# BT.net
KiCad netlist of a schematic drawn in Altium Designer
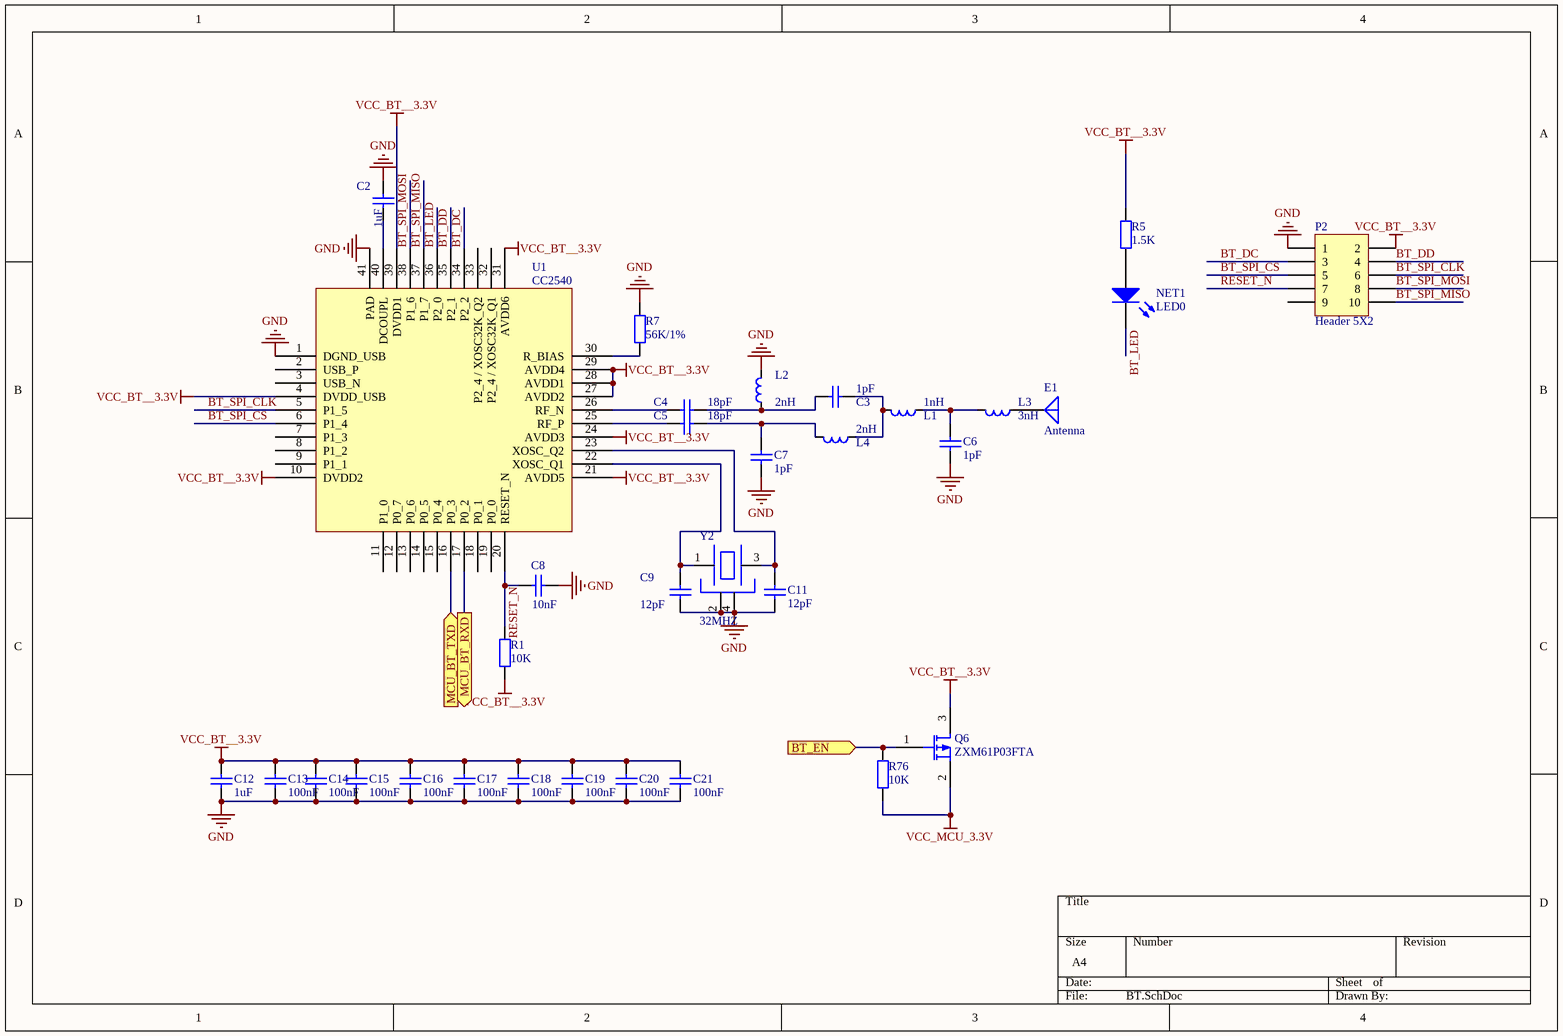
[diagram p0: BT.SchDoc]

(export (version "E")
  (design (tool "Eeschema 10.0.6"))
  (components
    (comp (ref "C2")
      (value "1uF")
      (footprint "0603C")
      (description "Capacitor")
      (fields (field (name "PUBLISHER") "Altium Limited"))
      (libsource (lib "Miscellaneous Devices") (part "Cap"))
    )
    (comp (ref "C3")
      (value "1pF")
      (footprint "0402C")
      (description "Capacitor")
      (fields (field (name "PUBLISHER") "Altium Limited"))
      (libsource (lib "Miscellaneous Devices") (part "Cap"))
    )
    (comp (ref "C4")
      (value "18pF")
      (footprint "0402C")
      (description "Capacitor")
      (fields (field (name "PUBLISHER") "Altium Limited"))
      (libsource (lib "Miscellaneous Devices") (part "Cap"))
    )
    (comp (ref "C5")
      (value "18pF")
      (footprint "0402C")
      (description "Capacitor")
      (fields (field (name "PUBLISHER") "Altium Limited"))
      (libsource (lib "Miscellaneous Devices") (part "Cap"))
    )
    (comp (ref "C6")
      (value "1pF")
      (footprint "0402C")
      (description "Capacitor")
      (fields (field (name "PUBLISHER") "Altium Limited"))
      (libsource (lib "Miscellaneous Devices") (part "Cap"))
    )
    (comp (ref "C7")
      (value "1pF")
      (footprint "0402C")
      (description "Capacitor")
      (fields (field (name "PUBLISHER") "Altium Limited"))
      (libsource (lib "Miscellaneous Devices") (part "Cap"))
    )
    (comp (ref "C8")
      (value "10nF")
      (footprint "0402C")
      (description "Capacitor")
      (fields (field (name "PUBLISHER") "Altium Limited"))
      (libsource (lib "Miscellaneous Devices") (part "Cap"))
    )
    (comp (ref "C9")
      (value "12pF")
      (footprint "0402C")
      (description "Capacitor")
      (fields (field (name "PUBLISHER") "Altium Limited"))
      (libsource (lib "Miscellaneous Devices") (part "Cap"))
    )
    (comp (ref "C11")
      (value "12pF")
      (footprint "0402C")
      (description "Capacitor")
      (fields (field (name "PUBLISHER") "Altium Limited"))
      (libsource (lib "Miscellaneous Devices") (part "Cap"))
    )
    (comp (ref "C12")
      (value "1uF")
      (footprint "0603C")
      (description "Capacitor")
      (fields (field (name "PUBLISHER") "Altium Limited"))
      (libsource (lib "Miscellaneous Devices") (part "Cap"))
    )
    (comp (ref "C13")
      (value "100nF")
      (footprint "0603C")
      (description "Capacitor")
      (fields (field (name "PUBLISHER") "Altium Limited"))
      (libsource (lib "Miscellaneous Devices") (part "Cap"))
    )
    (comp (ref "C14")
      (value "100nF")
      (footprint "0603C")
      (description "Capacitor")
      (fields (field (name "PUBLISHER") "Altium Limited"))
      (libsource (lib "Miscellaneous Devices") (part "Cap"))
    )
    (comp (ref "C15")
      (value "100nF")
      (footprint "0603C")
      (description "Capacitor")
      (fields (field (name "PUBLISHER") "Altium Limited"))
      (libsource (lib "Miscellaneous Devices") (part "Cap"))
    )
    (comp (ref "C16")
      (value "100nF")
      (footprint "0603C")
      (description "Capacitor")
      (fields (field (name "PUBLISHER") "Altium Limited"))
      (libsource (lib "Miscellaneous Devices") (part "Cap"))
    )
    (comp (ref "C17")
      (value "100nF")
      (footprint "0603C")
      (description "Capacitor")
      (fields (field (name "PUBLISHER") "Altium Limited"))
      (libsource (lib "Miscellaneous Devices") (part "Cap"))
    )
    (comp (ref "C18")
      (value "100nF")
      (footprint "0603C")
      (description "Capacitor")
      (fields (field (name "PUBLISHER") "Altium Limited"))
      (libsource (lib "Miscellaneous Devices") (part "Cap"))
    )
    (comp (ref "C19")
      (value "100nF")
      (footprint "0603C")
      (description "Capacitor")
      (fields (field (name "PUBLISHER") "Altium Limited"))
      (libsource (lib "Miscellaneous Devices") (part "Cap"))
    )
    (comp (ref "C20")
      (value "100nF")
      (footprint "0603C")
      (description "Capacitor")
      (fields (field (name "PUBLISHER") "Altium Limited"))
      (libsource (lib "Miscellaneous Devices") (part "Cap"))
    )
    (comp (ref "C21")
      (value "100nF")
      (footprint "0603C")
      (description "Capacitor")
      (fields (field (name "PUBLISHER") "Altium Limited"))
      (libsource (lib "Miscellaneous Devices") (part "Cap"))
    )
    (comp (ref "E1")
      (value "Antenna")
      (footprint "AN2051")
      (description "Generic Antenna")
      (fields (field (name "PUBLISHER") "Altium Limited"))
      (libsource (lib "Miscellaneous Devices") (part "Antenna"))
    )
    (comp (ref "L1") (value "1nH") (footprint "0402R") (description "L") (libsource (lib "*") (part "L_4")))
    (comp (ref "L2") (value "2nH") (footprint "0402R") (description "L") (libsource (lib "") (part "L_4_1")))
    (comp (ref "L3") (value "3nH") (footprint "0402R") (description "L") (libsource (lib "*") (part "L_4")))
    (comp (ref "L4") (value "2nH") (footprint "0402R") (description "L") (libsource (lib "*") (part "L_4")))
    (comp (ref "NET1")
      (value "LED0")
      (footprint "0603LED")
      (description "Typical INFRARED GaAs LED")
      (fields (field (name "PUBLISHER") "Altium Limited"))
      (libsource (lib "Miscellaneous Devices") (part "LED0"))
    )
    (comp (ref "P2")
      (value "Header 5X2")
      (footprint "HDR2X5")
      (description "Header, 5-Pin, Dual row")
      (fields (field (name "PUBLISHER") "Altium Limited"))
      (libsource (lib "Miscellaneous Connectors") (part "Header 5X2"))
    )
    (comp (ref "Q6")
      (value "ZXM61P03FTA")
      (footprint "SOT23-3")
      (description "ZXM61P03F")
      (fields (field (name "PUBLISHER") "Altium Limited"))
      (libsource (lib "Miscellaneous Devices") (part "MOSFET-P"))
    )
    (comp (ref "R1")
      (value "10K")
      (footprint "0603R")
      (description "Resistor")
      (fields (field (name "PUBLISHER") "Altium Limited"))
      (libsource (lib "Miscellaneous Devices") (part "Res2"))
    )
    (comp (ref "R5")
      (value "1.5K")
      (footprint "0603R")
      (description "Resistor")
      (fields (field (name "PUBLISHER") "Altium Limited"))
      (libsource (lib "Miscellaneous Devices") (part "Res2"))
    )
    (comp (ref "R7")
      (value "56K/1%")
      (footprint "0603R")
      (description "Resistor")
      (fields (field (name "PUBLISHER") "Altium Limited"))
      (libsource (lib "Miscellaneous Devices") (part "Res2"))
    )
    (comp (ref "R76")
      (value "10K")
      (footprint "0603R")
      (description "Resistor")
      (fields (field (name "PUBLISHER") "Altium Limited"))
      (libsource (lib "Miscellaneous Devices") (part "Res2"))
    )
    (comp (ref "U1")
      (value "CC2540")
      (footprint "QFN50P600X600X80-40N")
      (libsource (lib "stm32") (part "CC2540"))
    )
    (comp (ref "Y2")
      (value "32MHZ")
      (footprint "OSCILLATOR-3.2X2.5")
      (libsource (lib "Myself_1") (part "XTAL3"))
    )
  )
  (nets
    (net (code "1") (name "/BT_DC") (class "Default")
      (node (ref "P2") (pin "3") (pinfunction "3_3") (pintype "passive"))
      (node (ref "U1") (pin "34") (pinfunction "P2_2_34") (pintype "passive"))
    )
    (net (code "2") (name "/BT_DD") (class "Default")
      (node (ref "P2") (pin "4") (pinfunction "4_4") (pintype "passive"))
      (node (ref "U1") (pin "35") (pinfunction "P2_1_35") (pintype "passive"))
    )
    (net (code "3") (name "/BT_EN") (class "Default")
      (node (ref "Q6") (pin "1") (pinfunction "G_1") (pintype "passive"))
      (node (ref "R76") (pin "1") (pinfunction "1_1") (pintype "passive"))
    )
    (net (code "4") (name "/BT_LED") (class "Default")
      (node (ref "NET1") (pin "2") (pinfunction "K_2") (pintype "passive"))
      (node (ref "U1") (pin "36") (pinfunction "P2_0_36") (pintype "passive"))
    )
    (net (code "5") (name "/BT_SPI_CLK") (class "Default")
      (node (ref "P2") (pin "6") (pinfunction "6_6") (pintype "passive"))
      (node (ref "U1") (pin "5") (pinfunction "P1_5_5") (pintype "passive"))
    )
    (net (code "6") (name "/BT_SPI_CS") (class "Default")
      (node (ref "P2") (pin "5") (pinfunction "5_5") (pintype "passive"))
      (node (ref "U1") (pin "6") (pinfunction "P1_4_6") (pintype "passive"))
    )
    (net (code "7") (name "/BT_SPI_MISO") (class "Default")
      (node (ref "P2") (pin "10") (pinfunction "10_10") (pintype "passive"))
      (node (ref "U1") (pin "37") (pinfunction "P1_7_37") (pintype "passive"))
    )
    (net (code "8") (name "/BT_SPI_MOSI") (class "Default")
      (node (ref "P2") (pin "8") (pinfunction "8_8") (pintype "passive"))
      (node (ref "U1") (pin "38") (pinfunction "P1_6_38") (pintype "passive"))
    )
    (net (code "9") (name "/MCU_BT_RXD") (class "Default")
      (node (ref "U1") (pin "17") (pinfunction "P0_2_17") (pintype "passive"))
    )
    (net (code "10") (name "/MCU_BT_TXD") (class "Default")
      (node (ref "U1") (pin "16") (pinfunction "P0_3_16") (pintype "passive"))
    )
    (net (code "11") (name "/RESET_N") (class "Default")
      (node (ref "C8") (pin "2") (pinfunction "2_2") (pintype "passive"))
      (node (ref "P2") (pin "7") (pinfunction "7_7") (pintype "passive"))
      (node (ref "R1") (pin "1") (pinfunction "1_1") (pintype "passive"))
      (node (ref "U1") (pin "20") (pinfunction "RESET_N_20") (pintype "passive"))
    )
    (net (code "12") (name "GND") (class "Default")
      (node (ref "C11") (pin "1") (pinfunction "1_1") (pintype "passive"))
      (node (ref "C12") (pin "2") (pinfunction "2_2") (pintype "passive"))
      (node (ref "C13") (pin "2") (pinfunction "2_2") (pintype "passive"))
      (node (ref "C14") (pin "2") (pinfunction "2_2") (pintype "passive"))
      (node (ref "C15") (pin "2") (pinfunction "2_2") (pintype "passive"))
      (node (ref "C16") (pin "2") (pinfunction "2_2") (pintype "passive"))
      (node (ref "C17") (pin "2") (pinfunction "2_2") (pintype "passive"))
      (node (ref "C18") (pin "2") (pinfunction "2_2") (pintype "passive"))
      (node (ref "C19") (pin "2") (pinfunction "2_2") (pintype "passive"))
      (node (ref "C2") (pin "1") (pinfunction "1_1") (pintype "passive"))
      (node (ref "C20") (pin "2") (pinfunction "2_2") (pintype "passive"))
      (node (ref "C21") (pin "2") (pinfunction "2_2") (pintype "passive"))
      (node (ref "C6") (pin "1") (pinfunction "1_1") (pintype "passive"))
      (node (ref "C7") (pin "1") (pinfunction "1_1") (pintype "passive"))
      (node (ref "C8") (pin "1") (pinfunction "1_1") (pintype "passive"))
      (node (ref "C9") (pin "1") (pinfunction "1_1") (pintype "passive"))
      (node (ref "L2") (pin "2") (pintype "passive"))
      (node (ref "P2") (pin "1") (pinfunction "1_1") (pintype "passive"))
      (node (ref "R7") (pin "1") (pinfunction "1_1") (pintype "passive"))
      (node (ref "U1") (pin "1") (pinfunction "DGND_USB_1") (pintype "passive"))
      (node (ref "U1") (pin "41") (pinfunction "PAD_41") (pintype "passive"))
      (node (ref "Y2") (pin "2") (pinfunction "GND_2") (pintype "passive"))
      (node (ref "Y2") (pin "4") (pinfunction "GND_4") (pintype "passive"))
    )
    (net (code "13") (name "Net-(C3-Pad1)") (class "Default")
      (node (ref "C3") (pin "1") (pinfunction "1_1") (pintype "passive"))
      (node (ref "C4") (pin "2") (pinfunction "2_2") (pintype "passive"))
      (node (ref "L2") (pin "1") (pintype "passive"))
    )
    (net (code "14") (name "Net-(C3-Pad2)") (class "Default")
      (node (ref "C3") (pin "2") (pinfunction "2_2") (pintype "passive"))
      (node (ref "L1") (pin "2") (pintype "passive"))
      (node (ref "L4") (pin "1") (pintype "passive"))
    )
    (net (code "15") (name "Net-(C5-Pad2)") (class "Default")
      (node (ref "C5") (pin "2") (pinfunction "2_2") (pintype "passive"))
      (node (ref "C7") (pin "2") (pinfunction "2_2") (pintype "passive"))
      (node (ref "L4") (pin "2") (pintype "passive"))
    )
    (net (code "16") (name "Net-(C6-Pad2)") (class "Default")
      (node (ref "C6") (pin "2") (pinfunction "2_2") (pintype "passive"))
      (node (ref "L1") (pin "1") (pintype "passive"))
      (node (ref "L3") (pin "2") (pintype "passive"))
    )
    (net (code "17") (name "Net-(E1-A)") (class "Default")
      (node (ref "E1") (pin "1") (pinfunction "A_1") (pintype "passive"))
      (node (ref "L3") (pin "1") (pintype "passive"))
    )
    (net (code "18") (name "Net-(NET1-A)") (class "Default")
      (node (ref "NET1") (pin "1") (pinfunction "A_1") (pintype "passive"))
      (node (ref "R5") (pin "2") (pinfunction "2_2") (pintype "passive"))
    )
    (net (code "19") (name "Net-(U1-DCOUPL)") (class "Default")
      (node (ref "C2") (pin "2") (pinfunction "2_2") (pintype "passive"))
      (node (ref "U1") (pin "40") (pinfunction "DCOUPL_40") (pintype "passive"))
    )
    (net (code "20") (name "Net-(U1-RF_N)") (class "Default")
      (node (ref "C4") (pin "1") (pinfunction "1_1") (pintype "passive"))
      (node (ref "U1") (pin "26") (pinfunction "RF_N_26") (pintype "passive"))
    )
    (net (code "21") (name "Net-(U1-RF_P)") (class "Default")
      (node (ref "C5") (pin "1") (pinfunction "1_1") (pintype "passive"))
      (node (ref "U1") (pin "25") (pinfunction "RF_P_25") (pintype "passive"))
    )
    (net (code "22") (name "Net-(U1-R_BIAS)") (class "Default")
      (node (ref "R7") (pin "2") (pinfunction "2_2") (pintype "passive"))
      (node (ref "U1") (pin "30") (pinfunction "R_BIAS_30") (pintype "passive"))
    )
    (net (code "23") (name "Net-(U1-XOSC_Q1)") (class "Default")
      (node (ref "C9") (pin "2") (pinfunction "2_2") (pintype "passive"))
      (node (ref "U1") (pin "22") (pinfunction "XOSC_Q1_22") (pintype "passive"))
      (node (ref "Y2") (pin "1") (pinfunction "1_1") (pintype "passive"))
    )
    (net (code "24") (name "Net-(U1-XOSC_Q2)") (class "Default")
      (node (ref "C11") (pin "2") (pinfunction "2_2") (pintype "passive"))
      (node (ref "U1") (pin "23") (pinfunction "XOSC_Q2_23") (pintype "passive"))
      (node (ref "Y2") (pin "3") (pinfunction "3_3") (pintype "passive"))
    )
    (net (code "25") (name "VCC_BT__3.3V") (class "Default")
      (node (ref "C12") (pin "1") (pinfunction "1_1") (pintype "passive"))
      (node (ref "C13") (pin "1") (pinfunction "1_1") (pintype "passive"))
      (node (ref "C14") (pin "1") (pinfunction "1_1") (pintype "passive"))
      (node (ref "C15") (pin "1") (pinfunction "1_1") (pintype "passive"))
      (node (ref "C16") (pin "1") (pinfunction "1_1") (pintype "passive"))
      (node (ref "C17") (pin "1") (pinfunction "1_1") (pintype "passive"))
      (node (ref "C18") (pin "1") (pinfunction "1_1") (pintype "passive"))
      (node (ref "C19") (pin "1") (pinfunction "1_1") (pintype "passive"))
      (node (ref "C20") (pin "1") (pinfunction "1_1") (pintype "passive"))
      (node (ref "C21") (pin "1") (pinfunction "1_1") (pintype "passive"))
      (node (ref "P2") (pin "2") (pinfunction "2_2") (pintype "passive"))
      (node (ref "Q6") (pin "3") (pinfunction "S_3") (pintype "passive"))
      (node (ref "R1") (pin "2") (pinfunction "2_2") (pintype "passive"))
      (node (ref "R5") (pin "1") (pinfunction "1_1") (pintype "passive"))
      (node (ref "U1") (pin "10") (pinfunction "DVDD2_10") (pintype "passive"))
      (node (ref "U1") (pin "21") (pinfunction "AVDD5_21") (pintype "passive"))
      (node (ref "U1") (pin "24") (pinfunction "AVDD3_24") (pintype "passive"))
      (node (ref "U1") (pin "27") (pinfunction "AVDD2_27") (pintype "passive"))
      (node (ref "U1") (pin "28") (pinfunction "AVDD1_28") (pintype "passive"))
      (node (ref "U1") (pin "29") (pinfunction "AVDD4_29") (pintype "passive"))
      (node (ref "U1") (pin "31") (pinfunction "AVDD6_31") (pintype "passive"))
      (node (ref "U1") (pin "39") (pinfunction "DVDD1_39") (pintype "passive"))
      (node (ref "U1") (pin "4") (pinfunction "DVDD_USB_4") (pintype "passive"))
    )
    (net (code "26") (name "VCC_MCU_3.3V") (class "Default")
      (node (ref "Q6") (pin "2") (pinfunction "D_2") (pintype "passive"))
      (node (ref "R76") (pin "2") (pinfunction "2_2") (pintype "passive"))
    )
    (net (code "27") (name "unconnected-(P2-Pad9)") (class "Default")
      (node (ref "P2") (pin "9") (pinfunction "9_9") (pintype "passive"))
    )
    (net (code "28") (name "unconnected-(U1-P0_0-Pad19)") (class "Default")
      (node (ref "U1") (pin "19") (pinfunction "P0_0_19") (pintype "passive"))
    )
    (net (code "29") (name "unconnected-(U1-P0_1-Pad18)") (class "Default")
      (node (ref "U1") (pin "18") (pinfunction "P0_1_18") (pintype "passive"))
    )
    (net (code "30") (name "unconnected-(U1-P0_4-Pad15)") (class "Default")
      (node (ref "U1") (pin "15") (pinfunction "P0_4_15") (pintype "passive"))
    )
    (net (code "31") (name "unconnected-(U1-P0_5-Pad14)") (class "Default")
      (node (ref "U1") (pin "14") (pinfunction "P0_5_14") (pintype "passive"))
    )
    (net (code "32") (name "unconnected-(U1-P0_6-Pad13)") (class "Default")
      (node (ref "U1") (pin "13") (pinfunction "P0_6_13") (pintype "passive"))
    )
    (net (code "33") (name "unconnected-(U1-P0_7-Pad12)") (class "Default")
      (node (ref "U1") (pin "12") (pinfunction "P0_7_12") (pintype "passive"))
    )
    (net (code "34") (name "unconnected-(U1-P1_0-Pad11)") (class "Default")
      (node (ref "U1") (pin "11") (pinfunction "P1_0_11") (pintype "passive"))
    )
    (net (code "35") (name "unconnected-(U1-P1_1-Pad9)") (class "Default")
      (node (ref "U1") (pin "9") (pinfunction "P1_1_9") (pintype "passive"))
    )
    (net (code "36") (name "unconnected-(U1-P1_2-Pad8)") (class "Default")
      (node (ref "U1") (pin "8") (pinfunction "P1_2_8") (pintype "passive"))
    )
    (net (code "37") (name "unconnected-(U1-P1_3-Pad7)") (class "Default")
      (node (ref "U1") (pin "7") (pinfunction "P1_3_7") (pintype "passive"))
    )
    (net (code "38") (name "unconnected-(U1-P2_4_{slash}_XOSC32K_Q1-Pad32)") (class "Default")
      (node (ref "U1") (pin "32") (pinfunction "P2_4_/_XOSC32K_Q1_32") (pintype "passive"))
    )
    (net (code "39") (name "unconnected-(U1-P2_4_{slash}_XOSC32K_Q2-Pad33)") (class "Default")
      (node (ref "U1") (pin "33") (pinfunction "P2_4_/_XOSC32K_Q2_33") (pintype "passive"))
    )
    (net (code "40") (name "unconnected-(U1-USB_N-Pad3)") (class "Default")
      (node (ref "U1") (pin "3") (pinfunction "USB_N_3") (pintype "passive"))
    )
    (net (code "41") (name "unconnected-(U1-USB_P-Pad2)") (class "Default")
      (node (ref "U1") (pin "2") (pinfunction "USB_P_2") (pintype "passive"))
    )
  )
)
